# audio-mixer.net
KiCad netlist of a schematic drawn in EAGLE
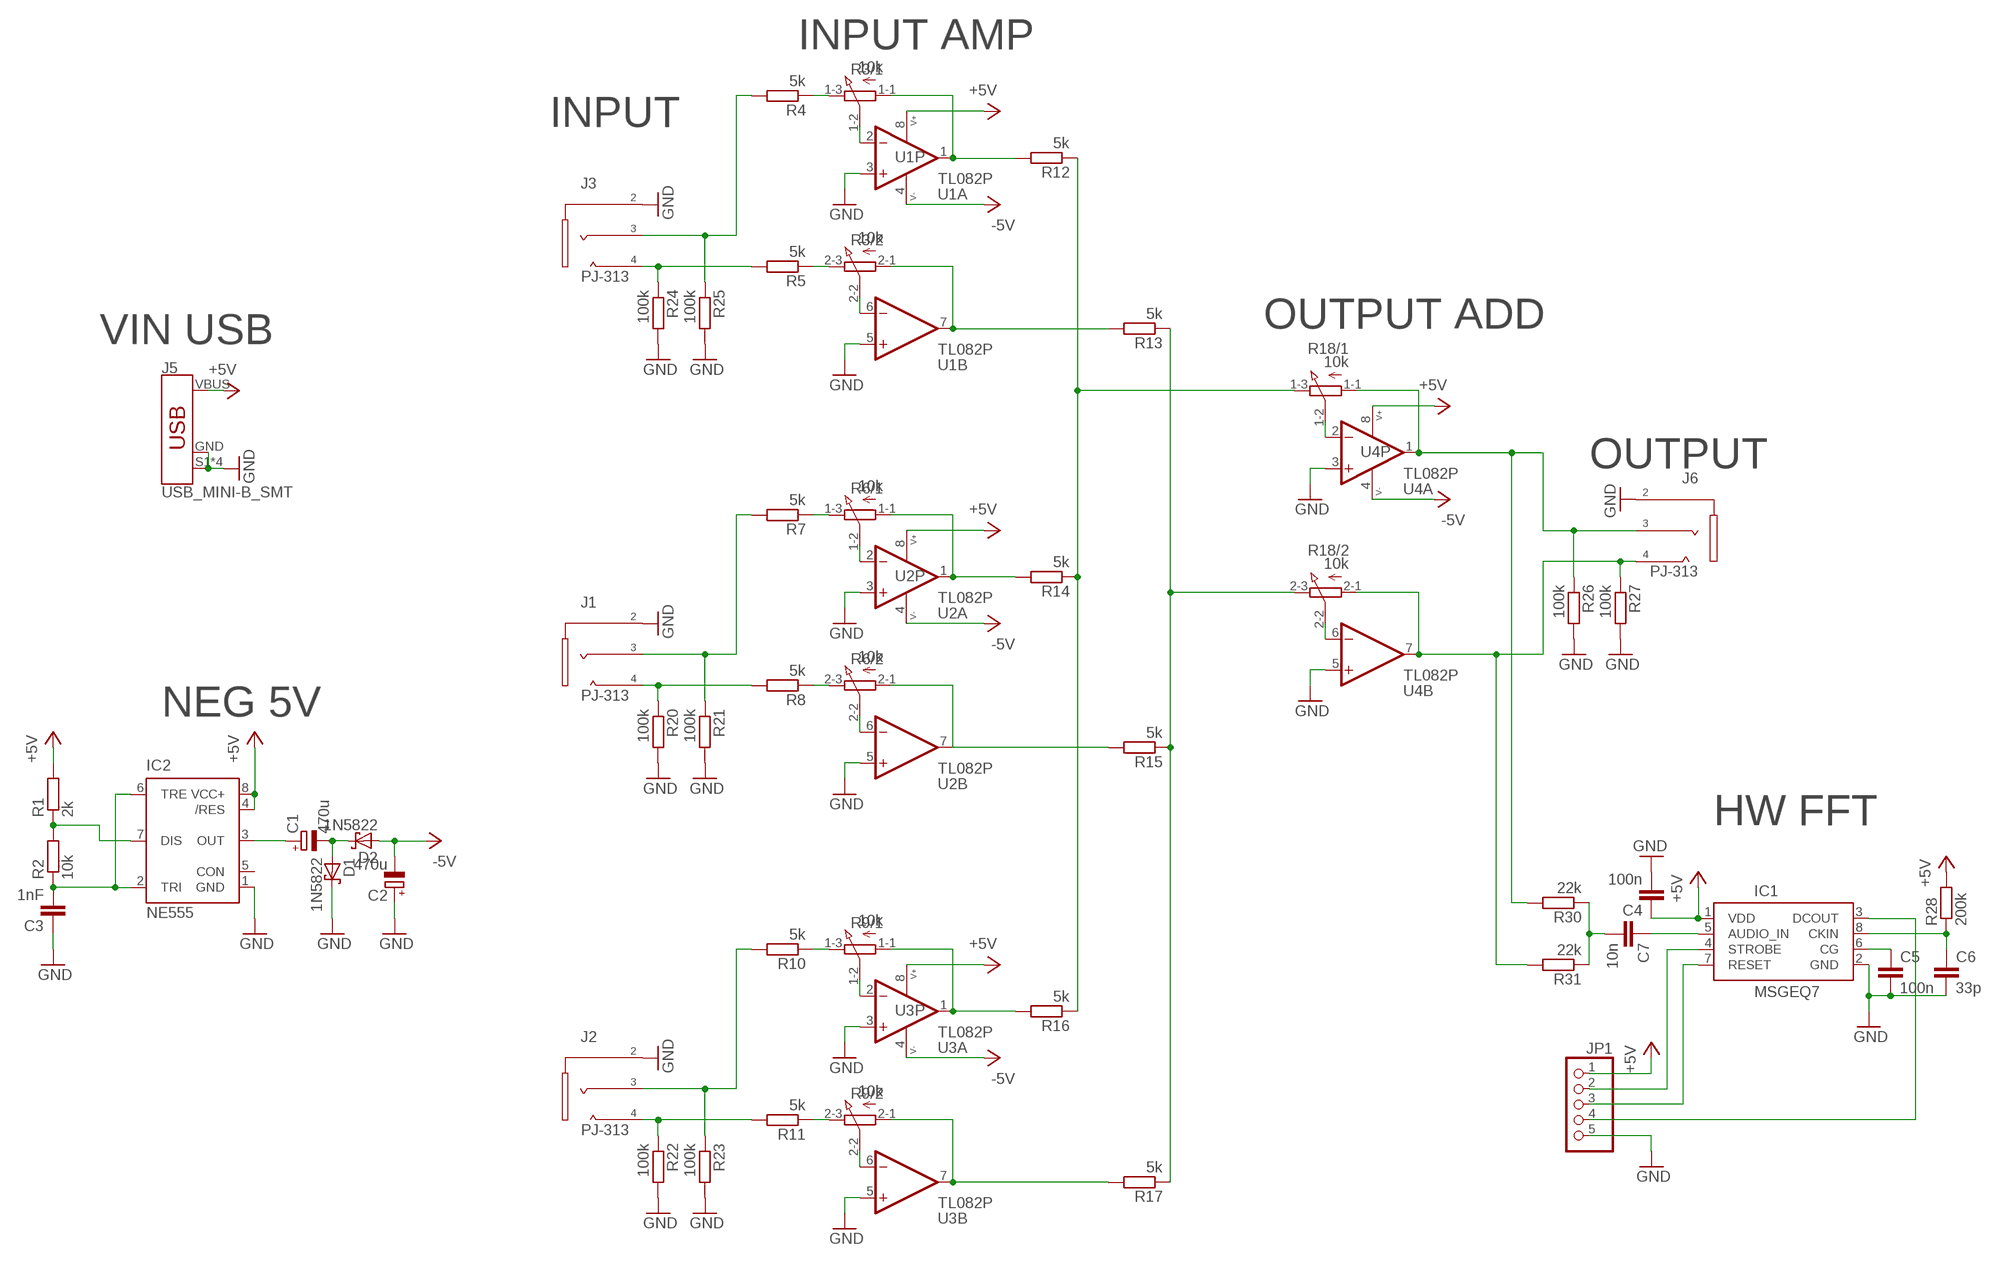
[diagram p0: schematic, sheet 1]

(export (version "E")
  (design (tool "Eeschema 10.0.6"))
  (components
    (comp (ref "C1")
      (value "470u")
      (footprint "eagle-import:E5-8,5")
      (libsource (lib "eagle-import") (part "CPOL-EUE5-8.5"))
    )
    (comp (ref "C2")
      (value "470u")
      (footprint "eagle-import:E5-8,5")
      (libsource (lib "eagle-import") (part "CPOL-EUE5-8.5"))
    )
    (comp (ref "C3")
      (value "1nF")
      (footprint "eagle-import:C025-025X050")
      (libsource (lib "eagle-import") (part "C-EU025-025X050"))
    )
    (comp (ref "C4")
      (value "100n")
      (footprint "eagle-import:C025-025X050")
      (libsource (lib "eagle-import") (part "C-EU025-025X050"))
    )
    (comp (ref "C5")
      (value "100n")
      (footprint "eagle-import:C025-025X050")
      (libsource (lib "eagle-import") (part "C-EU025-025X050"))
    )
    (comp (ref "C6")
      (value "33p")
      (footprint "eagle-import:C025-025X050")
      (libsource (lib "eagle-import") (part "C-EU025-025X050"))
    )
    (comp (ref "C7")
      (value "10n")
      (footprint "eagle-import:C025-025X050")
      (libsource (lib "eagle-import") (part "C-EU025-025X050"))
    )
    (comp (ref "D1")
      (value "1N5822")
      (footprint "eagle-import:DO41-7.6")
      (libsource (lib "eagle-import") (part "1N5817-B"))
    )
    (comp (ref "D2")
      (value "1N5822")
      (footprint "eagle-import:DO41-7.6")
      (libsource (lib "eagle-import") (part "1N5817-B"))
    )
    (comp (ref "IC1")
      (value "MSGEQ7DIP")
      (footprint "eagle-import:DIL08")
      (libsource (lib "eagle-import") (part "MSGEQ7DIP"))
    )
    (comp (ref "IC2")
      (value "NE555")
      (footprint "eagle-import:DIL-08")
      (fields (field (name "MF") "Arrow Electronics") (field (name "MPN") "NE555N"))
      (libsource (lib "eagle-import") (part "NE555"))
    )
    (comp (ref "J1")
      (value "PJ-313")
      (footprint "eagle-import:PJ-313")
      (libsource (lib "eagle-import") (part "PJ-313"))
    )
    (comp (ref "J2")
      (value "PJ-313")
      (footprint "eagle-import:PJ-313")
      (libsource (lib "eagle-import") (part "PJ-313"))
    )
    (comp (ref "J3")
      (value "PJ-313")
      (footprint "eagle-import:PJ-313")
      (libsource (lib "eagle-import") (part "PJ-313"))
    )
    (comp (ref "J5")
      (value "USB_MINI-B_SMT")
      (footprint "eagle-import:USB-MINIB")
      (libsource (lib "eagle-import") (part "USB_MINI-B_SMT"))
    )
    (comp (ref "J6")
      (value "PJ-313")
      (footprint "eagle-import:PJ-313")
      (libsource (lib "eagle-import") (part "PJ-313"))
    )
    (comp (ref "JP1")
      (value "PINHD-1X05_2.54-S")
      (footprint "eagle-import:1X05-S")
      (libsource (lib "eagle-import") (part "PINHD-1X05_2.54-S"))
    )
    (comp (ref "R1")
      (value "2k")
      (footprint "eagle-import:0207_10")
      (libsource (lib "eagle-import") (part "R-EU_0207/10"))
    )
    (comp (ref "R2")
      (value "10k")
      (footprint "eagle-import:0207_10")
      (libsource (lib "eagle-import") (part "R-EU_0207/10"))
    )
    (comp (ref "R3")
      (value "10k")
      (footprint "eagle-import:3RP_1610G")
      (libsource (lib "eagle-import") (part "3RP/1610G"))
    )
    (comp (ref "R4")
      (value "5k")
      (footprint "eagle-import:0207_10")
      (libsource (lib "eagle-import") (part "R-EU_0207/10"))
    )
    (comp (ref "R5")
      (value "5k")
      (footprint "eagle-import:0207_10")
      (libsource (lib "eagle-import") (part "R-EU_0207/10"))
    )
    (comp (ref "R6")
      (value "10k")
      (footprint "eagle-import:3RP_1610G")
      (libsource (lib "eagle-import") (part "3RP/1610G"))
    )
    (comp (ref "R7")
      (value "5k")
      (footprint "eagle-import:0207_10")
      (libsource (lib "eagle-import") (part "R-EU_0207/10"))
    )
    (comp (ref "R8")
      (value "5k")
      (footprint "eagle-import:0207_10")
      (libsource (lib "eagle-import") (part "R-EU_0207/10"))
    )
    (comp (ref "R9")
      (value "10k")
      (footprint "eagle-import:3RP_1610G")
      (libsource (lib "eagle-import") (part "3RP/1610G"))
    )
    (comp (ref "R10")
      (value "5k")
      (footprint "eagle-import:0207_10")
      (libsource (lib "eagle-import") (part "R-EU_0207/10"))
    )
    (comp (ref "R11")
      (value "5k")
      (footprint "eagle-import:0207_10")
      (libsource (lib "eagle-import") (part "R-EU_0207/10"))
    )
    (comp (ref "R12")
      (value "5k")
      (footprint "eagle-import:0207_10")
      (libsource (lib "eagle-import") (part "R-EU_0207/10"))
    )
    (comp (ref "R13")
      (value "5k")
      (footprint "eagle-import:0207_10")
      (libsource (lib "eagle-import") (part "R-EU_0207/10"))
    )
    (comp (ref "R14")
      (value "5k")
      (footprint "eagle-import:0207_10")
      (libsource (lib "eagle-import") (part "R-EU_0207/10"))
    )
    (comp (ref "R15")
      (value "5k")
      (footprint "eagle-import:0207_10")
      (libsource (lib "eagle-import") (part "R-EU_0207/10"))
    )
    (comp (ref "R16")
      (value "5k")
      (footprint "eagle-import:0207_10")
      (libsource (lib "eagle-import") (part "R-EU_0207/10"))
    )
    (comp (ref "R17")
      (value "5k")
      (footprint "eagle-import:0207_10")
      (libsource (lib "eagle-import") (part "R-EU_0207/10"))
    )
    (comp (ref "R18")
      (value "10k")
      (footprint "eagle-import:3RP_1610G")
      (libsource (lib "eagle-import") (part "3RP/1610G"))
    )
    (comp (ref "R20")
      (value "100k")
      (footprint "eagle-import:0207_10")
      (libsource (lib "eagle-import") (part "R-EU_0207/10"))
    )
    (comp (ref "R21")
      (value "100k")
      (footprint "eagle-import:0207_10")
      (libsource (lib "eagle-import") (part "R-EU_0207/10"))
    )
    (comp (ref "R22")
      (value "100k")
      (footprint "eagle-import:0207_10")
      (libsource (lib "eagle-import") (part "R-EU_0207/10"))
    )
    (comp (ref "R23")
      (value "100k")
      (footprint "eagle-import:0207_10")
      (libsource (lib "eagle-import") (part "R-EU_0207/10"))
    )
    (comp (ref "R24")
      (value "100k")
      (footprint "eagle-import:0207_10")
      (libsource (lib "eagle-import") (part "R-EU_0207/10"))
    )
    (comp (ref "R25")
      (value "100k")
      (footprint "eagle-import:0207_10")
      (libsource (lib "eagle-import") (part "R-EU_0207/10"))
    )
    (comp (ref "R26")
      (value "100k")
      (footprint "eagle-import:0207_10")
      (libsource (lib "eagle-import") (part "R-EU_0207/10"))
    )
    (comp (ref "R27")
      (value "100k")
      (footprint "eagle-import:0207_10")
      (libsource (lib "eagle-import") (part "R-EU_0207/10"))
    )
    (comp (ref "R28")
      (value "200k")
      (footprint "eagle-import:0207_10")
      (libsource (lib "eagle-import") (part "R-EU_0207/10"))
    )
    (comp (ref "R30")
      (value "22k")
      (footprint "eagle-import:0207_10")
      (libsource (lib "eagle-import") (part "R-EU_0207/10"))
    )
    (comp (ref "R31")
      (value "22k")
      (footprint "eagle-import:0207_10")
      (libsource (lib "eagle-import") (part "R-EU_0207/10"))
    )
    (comp (ref "U1")
      (value "TL082P")
      (footprint "eagle-import:DIL08")
      (libsource (lib "eagle-import") (part "TL082P"))
    )
    (comp (ref "U2")
      (value "TL082P")
      (footprint "eagle-import:DIL08")
      (libsource (lib "eagle-import") (part "TL082P"))
    )
    (comp (ref "U3")
      (value "TL082P")
      (footprint "eagle-import:DIL08")
      (libsource (lib "eagle-import") (part "TL082P"))
    )
    (comp (ref "U4")
      (value "TL082P")
      (footprint "eagle-import:DIL08")
      (libsource (lib "eagle-import") (part "TL082P"))
    )
  )
  (nets
    (net (code "1") (name "+5V") (class "Default")
      (node (ref "C4") (pin "1") (pinfunction "1_1") (pintype "passive"))
      (node (ref "IC1") (pin "1") (pinfunction "VDD_1") (pintype "input"))
      (node (ref "IC2") (pin "4") (pinfunction "/RES_4") (pintype "input"))
      (node (ref "IC2") (pin "8") (pinfunction "VCC+_8") (pintype "power_in"))
      (node (ref "J5") (pin "VBUS") (pinfunction "VBUS_VBUS") (pintype "power_in"))
      (node (ref "JP1") (pin "1") (pinfunction "1_1") (pintype "passive"))
      (node (ref "R1") (pin "2") (pinfunction "2_2") (pintype "passive"))
      (node (ref "R28") (pin "2") (pinfunction "2_2") (pintype "passive"))
      (node (ref "U1") (pin "8") (pinfunction "V+_8") (pintype "power_in"))
      (node (ref "U2") (pin "8") (pinfunction "V+_8") (pintype "power_in"))
      (node (ref "U3") (pin "8") (pinfunction "V+_8") (pintype "power_in"))
      (node (ref "U4") (pin "8") (pinfunction "V+_8") (pintype "power_in"))
    )
    (net (code "2") (name "-5V") (class "Default")
      (node (ref "C2") (pin "-") (pinfunction "-_-") (pintype "passive"))
      (node (ref "D2") (pin "A") (pinfunction "A_A") (pintype "passive"))
      (node (ref "U1") (pin "4") (pinfunction "V-_4") (pintype "power_in"))
      (node (ref "U2") (pin "4") (pinfunction "V-_4") (pintype "power_in"))
      (node (ref "U3") (pin "4") (pinfunction "V-_4") (pintype "power_in"))
      (node (ref "U4") (pin "4") (pinfunction "V-_4") (pintype "power_in"))
    )
    (net (code "3") (name "GND") (class "Default")
      (node (ref "C2") (pin "+") (pinfunction "+_+") (pintype "passive"))
      (node (ref "C3") (pin "1") (pinfunction "1_1") (pintype "passive"))
      (node (ref "C4") (pin "2") (pinfunction "2_2") (pintype "passive"))
      (node (ref "C5") (pin "2") (pinfunction "2_2") (pintype "passive"))
      (node (ref "C6") (pin "2") (pinfunction "2_2") (pintype "passive"))
      (node (ref "D1") (pin "C") (pinfunction "C_C") (pintype "passive"))
      (node (ref "IC1") (pin "2") (pinfunction "GND_2") (pintype "bidirectional"))
      (node (ref "IC2") (pin "1") (pinfunction "GND_1") (pintype "power_in"))
      (node (ref "J1") (pin "2_1") (pinfunction "2_2_1") (pintype "passive"))
      (node (ref "J1") (pin "2_2") (pinfunction "2_2_2") (pintype "passive"))
      (node (ref "J2") (pin "2_1") (pinfunction "2_2_1") (pintype "passive"))
      (node (ref "J2") (pin "2_2") (pinfunction "2_2_2") (pintype "passive"))
      (node (ref "J3") (pin "2_1") (pinfunction "2_2_1") (pintype "passive"))
      (node (ref "J3") (pin "2_2") (pinfunction "2_2_2") (pintype "passive"))
      (node (ref "J5") (pin "GND") (pinfunction "GND_GND") (pintype "power_in"))
      (node (ref "J5") (pin "S1") (pinfunction "SHIELD_S1") (pintype "bidirectional"))
      (node (ref "J5") (pin "S2") (pinfunction "SHIELD_S2") (pintype "bidirectional"))
      (node (ref "J5") (pin "S3") (pinfunction "SHIELD_S3") (pintype "bidirectional"))
      (node (ref "J5") (pin "S4") (pinfunction "SHIELD_S4") (pintype "bidirectional"))
      (node (ref "J6") (pin "2_1") (pinfunction "2_2_1") (pintype "passive"))
      (node (ref "J6") (pin "2_2") (pinfunction "2_2_2") (pintype "passive"))
      (node (ref "JP1") (pin "5") (pinfunction "5_5") (pintype "passive"))
      (node (ref "R20") (pin "2") (pinfunction "2_2") (pintype "passive"))
      (node (ref "R21") (pin "2") (pinfunction "2_2") (pintype "passive"))
      (node (ref "R22") (pin "2") (pinfunction "2_2") (pintype "passive"))
      (node (ref "R23") (pin "2") (pinfunction "2_2") (pintype "passive"))
      (node (ref "R24") (pin "2") (pinfunction "2_2") (pintype "passive"))
      (node (ref "R25") (pin "2") (pinfunction "2_2") (pintype "passive"))
      (node (ref "R26") (pin "2") (pinfunction "2_2") (pintype "passive"))
      (node (ref "R27") (pin "2") (pinfunction "2_2") (pintype "passive"))
      (node (ref "U1") (pin "3") (pinfunction "+IN_3") (pintype "input"))
      (node (ref "U1") (pin "5") (pinfunction "+IN_5") (pintype "input"))
      (node (ref "U2") (pin "3") (pinfunction "+IN_3") (pintype "input"))
      (node (ref "U2") (pin "5") (pinfunction "+IN_5") (pintype "input"))
      (node (ref "U3") (pin "3") (pinfunction "+IN_3") (pintype "input"))
      (node (ref "U3") (pin "5") (pinfunction "+IN_5") (pintype "input"))
      (node (ref "U4") (pin "3") (pinfunction "+IN_3") (pintype "input"))
      (node (ref "U4") (pin "5") (pinfunction "+IN_5") (pintype "input"))
    )
    (net (code "4") (name "Net-(C1-Pad-)") (class "Default")
      (node (ref "C1") (pin "-") (pinfunction "-_-") (pintype "passive"))
      (node (ref "D1") (pin "A") (pinfunction "A_A") (pintype "passive"))
      (node (ref "D2") (pin "C") (pinfunction "C_C") (pintype "passive"))
    )
    (net (code "5") (name "Net-(C7-Pad2)") (class "Default")
      (node (ref "C7") (pin "2") (pinfunction "2_2") (pintype "passive"))
      (node (ref "R30") (pin "1") (pinfunction "1_1") (pintype "passive"))
      (node (ref "R31") (pin "1") (pinfunction "1_1") (pintype "passive"))
    )
    (net (code "6") (name "Net-(IC1-AUDIO_IN)") (class "Default")
      (node (ref "C7") (pin "1") (pinfunction "1_1") (pintype "passive"))
      (node (ref "IC1") (pin "5") (pinfunction "AUDIO_IN_5") (pintype "input"))
    )
    (net (code "7") (name "Net-(IC1-CG)") (class "Default")
      (node (ref "C5") (pin "1") (pinfunction "1_1") (pintype "passive"))
      (node (ref "IC1") (pin "6") (pinfunction "CG_6") (pintype "bidirectional"))
    )
    (net (code "8") (name "Net-(IC1-CKIN)") (class "Default")
      (node (ref "C6") (pin "1") (pinfunction "1_1") (pintype "passive"))
      (node (ref "IC1") (pin "8") (pinfunction "CKIN_8") (pintype "bidirectional"))
      (node (ref "R28") (pin "1") (pinfunction "1_1") (pintype "passive"))
    )
    (net (code "9") (name "Net-(IC1-DCOUT)") (class "Default")
      (node (ref "IC1") (pin "3") (pinfunction "DCOUT_3") (pintype "bidirectional"))
      (node (ref "JP1") (pin "4") (pinfunction "4_4") (pintype "passive"))
    )
    (net (code "10") (name "Net-(IC1-RESET)") (class "Default")
      (node (ref "IC1") (pin "7") (pinfunction "RESET_7") (pintype "input"))
      (node (ref "JP1") (pin "3") (pinfunction "3_3") (pintype "passive"))
    )
    (net (code "11") (name "Net-(IC1-STROBE)") (class "Default")
      (node (ref "IC1") (pin "4") (pinfunction "STROBE_4") (pintype "input"))
      (node (ref "JP1") (pin "2") (pinfunction "2_2") (pintype "passive"))
    )
    (net (code "12") (name "Net-(IC2-DIS)") (class "Default")
      (node (ref "IC2") (pin "7") (pinfunction "DIS_7") (pintype "input"))
      (node (ref "R1") (pin "1") (pinfunction "1_1") (pintype "passive"))
      (node (ref "R2") (pin "2") (pinfunction "2_2") (pintype "passive"))
    )
    (net (code "13") (name "Net-(IC2-OUT)") (class "Default")
      (node (ref "C1") (pin "+") (pinfunction "+_+") (pintype "passive"))
      (node (ref "IC2") (pin "3") (pinfunction "OUT_3") (pintype "output"))
    )
    (net (code "14") (name "Net-(IC2-TRE)") (class "Default")
      (node (ref "C3") (pin "2") (pinfunction "2_2") (pintype "passive"))
      (node (ref "IC2") (pin "2") (pinfunction "TRI_2") (pintype "input"))
      (node (ref "IC2") (pin "6") (pinfunction "TRE_6") (pintype "input"))
      (node (ref "R2") (pin "1") (pinfunction "1_1") (pintype "passive"))
    )
    (net (code "15") (name "Net-(J1-4-Pad4_1)") (class "Default")
      (node (ref "J1") (pin "4_1") (pinfunction "4_4_1") (pintype "passive"))
      (node (ref "J1") (pin "4_2") (pinfunction "4_4_2") (pintype "passive"))
      (node (ref "R20") (pin "1") (pinfunction "1_1") (pintype "passive"))
      (node (ref "R8") (pin "2") (pinfunction "2_2") (pintype "passive"))
    )
    (net (code "16") (name "Net-(J1-Pad3)") (class "Default")
      (node (ref "J1") (pin "3") (pinfunction "3_3") (pintype "passive"))
      (node (ref "R21") (pin "1") (pinfunction "1_1") (pintype "passive"))
      (node (ref "R7") (pin "2") (pinfunction "2_2") (pintype "passive"))
    )
    (net (code "17") (name "Net-(J2-4-Pad4_1)") (class "Default")
      (node (ref "J2") (pin "4_1") (pinfunction "4_4_1") (pintype "passive"))
      (node (ref "J2") (pin "4_2") (pinfunction "4_4_2") (pintype "passive"))
      (node (ref "R11") (pin "2") (pinfunction "2_2") (pintype "passive"))
      (node (ref "R22") (pin "1") (pinfunction "1_1") (pintype "passive"))
    )
    (net (code "18") (name "Net-(J2-Pad3)") (class "Default")
      (node (ref "J2") (pin "3") (pinfunction "3_3") (pintype "passive"))
      (node (ref "R10") (pin "2") (pinfunction "2_2") (pintype "passive"))
      (node (ref "R23") (pin "1") (pinfunction "1_1") (pintype "passive"))
    )
    (net (code "19") (name "Net-(J3-4-Pad4_1)") (class "Default")
      (node (ref "J3") (pin "4_1") (pinfunction "4_4_1") (pintype "passive"))
      (node (ref "J3") (pin "4_2") (pinfunction "4_4_2") (pintype "passive"))
      (node (ref "R24") (pin "1") (pinfunction "1_1") (pintype "passive"))
      (node (ref "R5") (pin "2") (pinfunction "2_2") (pintype "passive"))
    )
    (net (code "20") (name "Net-(J3-Pad3)") (class "Default")
      (node (ref "J3") (pin "3") (pinfunction "3_3") (pintype "passive"))
      (node (ref "R25") (pin "1") (pinfunction "1_1") (pintype "passive"))
      (node (ref "R4") (pin "2") (pinfunction "2_2") (pintype "passive"))
    )
    (net (code "21") (name "Net-(R3A-A)") (class "Default")
      (node (ref "R12") (pin "2") (pinfunction "2_2") (pintype "passive"))
      (node (ref "R3") (pin "1-1") (pinfunction "A_1-1") (pintype "passive"))
      (node (ref "U1") (pin "1") (pinfunction "OUT_1") (pintype "output"))
    )
    (net (code "22") (name "Net-(R3A-E)") (class "Default")
      (node (ref "R3") (pin "1-3") (pinfunction "E_1-3") (pintype "passive"))
      (node (ref "R4") (pin "1") (pinfunction "1_1") (pintype "passive"))
    )
    (net (code "23") (name "Net-(R3A-S)") (class "Default")
      (node (ref "R3") (pin "1-2") (pinfunction "S_1-2") (pintype "passive"))
      (node (ref "U1") (pin "2") (pinfunction "-IN_2") (pintype "input"))
    )
    (net (code "24") (name "Net-(R3B-A)") (class "Default")
      (node (ref "R13") (pin "2") (pinfunction "2_2") (pintype "passive"))
      (node (ref "R3") (pin "2-1") (pinfunction "A_2-1") (pintype "passive"))
      (node (ref "U1") (pin "7") (pinfunction "OUT_7") (pintype "output"))
    )
    (net (code "25") (name "Net-(R3B-E)") (class "Default")
      (node (ref "R3") (pin "2-3") (pinfunction "E_2-3") (pintype "passive"))
      (node (ref "R5") (pin "1") (pinfunction "1_1") (pintype "passive"))
    )
    (net (code "26") (name "Net-(R3B-S)") (class "Default")
      (node (ref "R3") (pin "2-2") (pinfunction "S_2-2") (pintype "passive"))
      (node (ref "U1") (pin "6") (pinfunction "-IN_6") (pintype "input"))
    )
    (net (code "27") (name "Net-(R6A-A)") (class "Default")
      (node (ref "R14") (pin "2") (pinfunction "2_2") (pintype "passive"))
      (node (ref "R6") (pin "1-1") (pinfunction "A_1-1") (pintype "passive"))
      (node (ref "U2") (pin "1") (pinfunction "OUT_1") (pintype "output"))
    )
    (net (code "28") (name "Net-(R6A-E)") (class "Default")
      (node (ref "R6") (pin "1-3") (pinfunction "E_1-3") (pintype "passive"))
      (node (ref "R7") (pin "1") (pinfunction "1_1") (pintype "passive"))
    )
    (net (code "29") (name "Net-(R6A-S)") (class "Default")
      (node (ref "R6") (pin "1-2") (pinfunction "S_1-2") (pintype "passive"))
      (node (ref "U2") (pin "2") (pinfunction "-IN_2") (pintype "input"))
    )
    (net (code "30") (name "Net-(R6B-A)") (class "Default")
      (node (ref "R15") (pin "2") (pinfunction "2_2") (pintype "passive"))
      (node (ref "R6") (pin "2-1") (pinfunction "A_2-1") (pintype "passive"))
      (node (ref "U2") (pin "7") (pinfunction "OUT_7") (pintype "output"))
    )
    (net (code "31") (name "Net-(R6B-E)") (class "Default")
      (node (ref "R6") (pin "2-3") (pinfunction "E_2-3") (pintype "passive"))
      (node (ref "R8") (pin "1") (pinfunction "1_1") (pintype "passive"))
    )
    (net (code "32") (name "Net-(R6B-S)") (class "Default")
      (node (ref "R6") (pin "2-2") (pinfunction "S_2-2") (pintype "passive"))
      (node (ref "U2") (pin "6") (pinfunction "-IN_6") (pintype "input"))
    )
    (net (code "33") (name "Net-(R9A-A)") (class "Default")
      (node (ref "R16") (pin "2") (pinfunction "2_2") (pintype "passive"))
      (node (ref "R9") (pin "1-1") (pinfunction "A_1-1") (pintype "passive"))
      (node (ref "U3") (pin "1") (pinfunction "OUT_1") (pintype "output"))
    )
    (net (code "34") (name "Net-(R9A-E)") (class "Default")
      (node (ref "R10") (pin "1") (pinfunction "1_1") (pintype "passive"))
      (node (ref "R9") (pin "1-3") (pinfunction "E_1-3") (pintype "passive"))
    )
    (net (code "35") (name "Net-(R9A-S)") (class "Default")
      (node (ref "R9") (pin "1-2") (pinfunction "S_1-2") (pintype "passive"))
      (node (ref "U3") (pin "2") (pinfunction "-IN_2") (pintype "input"))
    )
    (net (code "36") (name "Net-(R9B-A)") (class "Default")
      (node (ref "R17") (pin "2") (pinfunction "2_2") (pintype "passive"))
      (node (ref "R9") (pin "2-1") (pinfunction "A_2-1") (pintype "passive"))
      (node (ref "U3") (pin "7") (pinfunction "OUT_7") (pintype "output"))
    )
    (net (code "37") (name "Net-(R9B-E)") (class "Default")
      (node (ref "R11") (pin "1") (pinfunction "1_1") (pintype "passive"))
      (node (ref "R9") (pin "2-3") (pinfunction "E_2-3") (pintype "passive"))
    )
    (net (code "38") (name "Net-(R9B-S)") (class "Default")
      (node (ref "R9") (pin "2-2") (pinfunction "S_2-2") (pintype "passive"))
      (node (ref "U3") (pin "6") (pinfunction "-IN_6") (pintype "input"))
    )
    (net (code "39") (name "Net-(R18A-A)") (class "Default")
      (node (ref "J6") (pin "3") (pinfunction "3_3") (pintype "passive"))
      (node (ref "R18") (pin "1-1") (pinfunction "A_1-1") (pintype "passive"))
      (node (ref "R26") (pin "1") (pinfunction "1_1") (pintype "passive"))
      (node (ref "R30") (pin "2") (pinfunction "2_2") (pintype "passive"))
      (node (ref "U4") (pin "1") (pinfunction "OUT_1") (pintype "output"))
    )
    (net (code "40") (name "Net-(R18A-E)") (class "Default")
      (node (ref "R12") (pin "1") (pinfunction "1_1") (pintype "passive"))
      (node (ref "R14") (pin "1") (pinfunction "1_1") (pintype "passive"))
      (node (ref "R16") (pin "1") (pinfunction "1_1") (pintype "passive"))
      (node (ref "R18") (pin "1-3") (pinfunction "E_1-3") (pintype "passive"))
    )
    (net (code "41") (name "Net-(R18A-S)") (class "Default")
      (node (ref "R18") (pin "1-2") (pinfunction "S_1-2") (pintype "passive"))
      (node (ref "U4") (pin "2") (pinfunction "-IN_2") (pintype "input"))
    )
    (net (code "42") (name "Net-(R18B-A)") (class "Default")
      (node (ref "J6") (pin "4_1") (pinfunction "4_4_1") (pintype "passive"))
      (node (ref "J6") (pin "4_2") (pinfunction "4_4_2") (pintype "passive"))
      (node (ref "R18") (pin "2-1") (pinfunction "A_2-1") (pintype "passive"))
      (node (ref "R27") (pin "1") (pinfunction "1_1") (pintype "passive"))
      (node (ref "R31") (pin "2") (pinfunction "2_2") (pintype "passive"))
      (node (ref "U4") (pin "7") (pinfunction "OUT_7") (pintype "output"))
    )
    (net (code "43") (name "Net-(R18B-E)") (class "Default")
      (node (ref "R13") (pin "1") (pinfunction "1_1") (pintype "passive"))
      (node (ref "R15") (pin "1") (pinfunction "1_1") (pintype "passive"))
      (node (ref "R17") (pin "1") (pinfunction "1_1") (pintype "passive"))
      (node (ref "R18") (pin "2-3") (pinfunction "E_2-3") (pintype "passive"))
    )
    (net (code "44") (name "Net-(R18B-S)") (class "Default")
      (node (ref "R18") (pin "2-2") (pinfunction "S_2-2") (pintype "passive"))
      (node (ref "U4") (pin "6") (pinfunction "-IN_6") (pintype "input"))
    )
    (net (code "45") (name "unconnected-(IC2-CON-Pad5)") (class "Default")
      (node (ref "IC2") (pin "5") (pinfunction "CON_5") (pintype "input"))
    )
  )
)
